# arm_shield_design_bottom_only.net
KiCad netlist of a schematic drawn in EAGLE
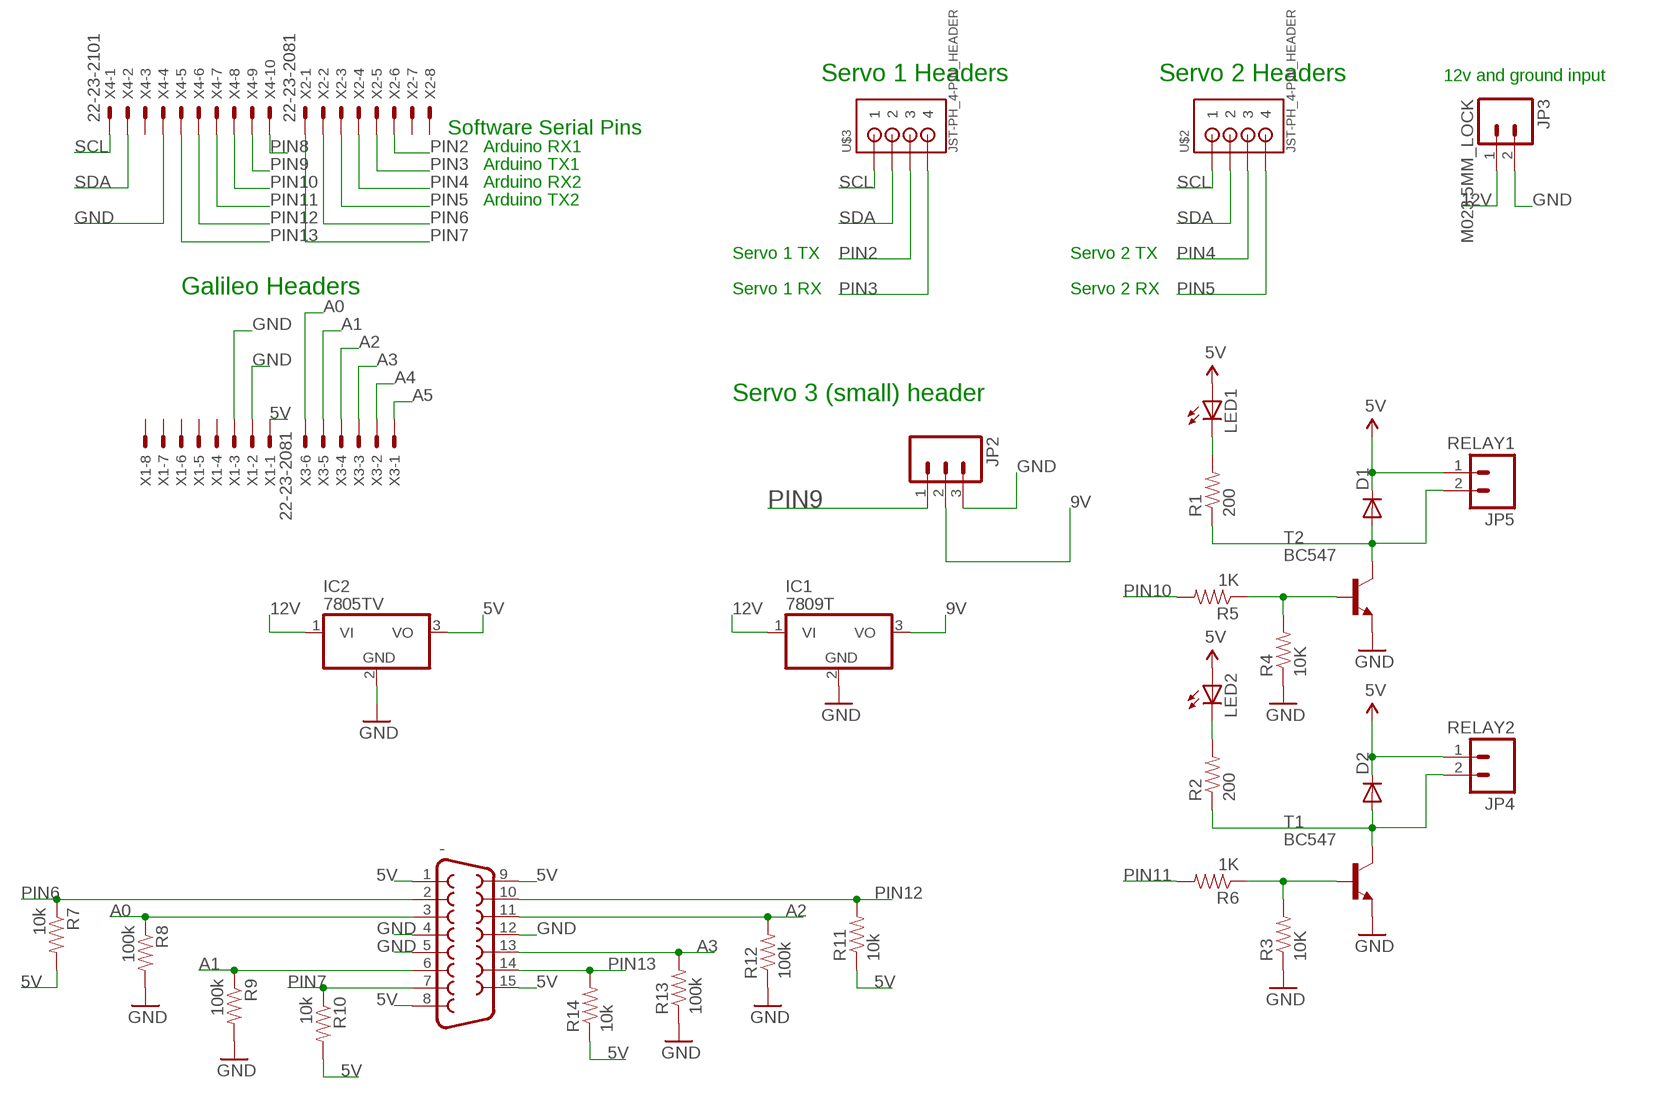
[diagram p0: schematic, sheet 1]

(export (version "E")
  (design (tool "Eeschema 10.0.6"))
  (components
    (comp (ref "-")
      (value "F15HP")
      (footprint "eagle-import:F15HP")
      (libsource (lib "eagle-import") (part "F15HP"))
    )
    (comp (ref "D1")
      (value "DIODE1N4148")
      (footprint "eagle-import:DIODE-1N4148")
      (libsource (lib "eagle-import") (part "DIODE1N4148"))
    )
    (comp (ref "D2")
      (value "DIODE1N4148")
      (footprint "eagle-import:DIODE-1N4148")
      (libsource (lib "eagle-import") (part "DIODE1N4148"))
    )
    (comp (ref "IC1")
      (value "7809T")
      (footprint "eagle-import:TO220V")
      (libsource (lib "eagle-import") (part "78TV05"))
    )
    (comp (ref "IC2")
      (value "7805TV")
      (footprint "eagle-import:TO220V")
      (libsource (lib "eagle-import") (part "78TV05"))
    )
    (comp (ref "JP2")
      (value "M03PTH")
      (footprint "eagle-import:1X03")
      (libsource (lib "eagle-import") (part "M03PTH"))
    )
    (comp (ref "JP3")
      (value "M023.5MM_LOCK")
      (footprint "eagle-import:SCREWTERMINAL-3.5MM-2_LOCK")
      (libsource (lib "eagle-import") (part "M023.5MM_LOCK"))
    )
    (comp (ref "JP4")
      (value "RELAY2")
      (footprint "eagle-import:SCREWTERMINAL-3.5MM-2_LOCK")
      (libsource (lib "eagle-import") (part "M023.5MM_LOCK"))
    )
    (comp (ref "JP5")
      (value "RELAY1")
      (footprint "eagle-import:SCREWTERMINAL-3.5MM-2_LOCK")
      (libsource (lib "eagle-import") (part "M023.5MM_LOCK"))
    )
    (comp (ref "LED1")
      (value "LED3MM")
      (footprint "eagle-import:LED3MM")
      (libsource (lib "eagle-import") (part "LED3MM"))
    )
    (comp (ref "LED2")
      (value "LED3MM")
      (footprint "eagle-import:LED3MM")
      (libsource (lib "eagle-import") (part "LED3MM"))
    )
    (comp (ref "R1")
      (value "200")
      (footprint "eagle-import:AXIAL-0.1")
      (libsource (lib "eagle-import") (part "RESISTORPTH-1/4W-VERT"))
    )
    (comp (ref "R2")
      (value "200")
      (footprint "eagle-import:AXIAL-0.1")
      (libsource (lib "eagle-import") (part "RESISTORPTH-1/4W-VERT"))
    )
    (comp (ref "R3")
      (value "10K")
      (footprint "eagle-import:AXIAL-0.1")
      (libsource (lib "eagle-import") (part "RESISTORPTH-1/4W-VERT"))
    )
    (comp (ref "R4")
      (value "10K")
      (footprint "eagle-import:AXIAL-0.1")
      (libsource (lib "eagle-import") (part "RESISTORPTH-1/4W-VERT"))
    )
    (comp (ref "R5")
      (value "1K")
      (footprint "eagle-import:AXIAL-0.1")
      (libsource (lib "eagle-import") (part "RESISTORPTH-1/4W-VERT"))
    )
    (comp (ref "R6")
      (value "1K")
      (footprint "eagle-import:AXIAL-0.1")
      (libsource (lib "eagle-import") (part "RESISTORPTH-1/4W-VERT"))
    )
    (comp (ref "R7")
      (value "10k")
      (footprint "eagle-import:AXIAL-0.1")
      (libsource (lib "eagle-import") (part "RESISTORPTH-1/4W-VERT"))
    )
    (comp (ref "R8")
      (value "100k")
      (footprint "eagle-import:AXIAL-0.1")
      (libsource (lib "eagle-import") (part "RESISTORPTH-1/4W-VERT"))
    )
    (comp (ref "R9")
      (value "100k")
      (footprint "eagle-import:AXIAL-0.1")
      (libsource (lib "eagle-import") (part "RESISTORPTH-1/4W-VERT"))
    )
    (comp (ref "R10")
      (value "10k")
      (footprint "eagle-import:AXIAL-0.1")
      (libsource (lib "eagle-import") (part "RESISTORPTH-1/4W-VERT"))
    )
    (comp (ref "R11")
      (value "10k")
      (footprint "eagle-import:AXIAL-0.1")
      (libsource (lib "eagle-import") (part "RESISTORPTH-1/4W-VERT"))
    )
    (comp (ref "R12")
      (value "100k")
      (footprint "eagle-import:AXIAL-0.1")
      (libsource (lib "eagle-import") (part "RESISTORPTH-1/4W-VERT"))
    )
    (comp (ref "R13")
      (value "100k")
      (footprint "eagle-import:AXIAL-0.1")
      (libsource (lib "eagle-import") (part "RESISTORPTH-1/4W-VERT"))
    )
    (comp (ref "R14")
      (value "10k")
      (footprint "eagle-import:AXIAL-0.1")
      (libsource (lib "eagle-import") (part "RESISTORPTH-1/4W-VERT"))
    )
    (comp (ref "T1")
      (value "BC547")
      (footprint "eagle-import:TO92")
      (libsource (lib "eagle-import") (part "BC547"))
    )
    (comp (ref "T2")
      (value "BC547")
      (footprint "eagle-import:TO92")
      (libsource (lib "eagle-import") (part "BC547"))
    )
    (comp (ref "U$2")
      (value "JST-PH_4-PIN_HEADER")
      (footprint "eagle-import:JST_B4B-PH_HEADER")
      (fields (field (name "MPN") "S4B-PH-K-S(LF)(SN)"))
      (libsource (lib "eagle-import") (part "JST-PH_4-PIN_HEADER"))
    )
    (comp (ref "U$3")
      (value "JST-PH_4-PIN_HEADER")
      (footprint "eagle-import:JST_B4B-PH_HEADER")
      (fields (field (name "MPN") "S4B-PH-K-S(LF)(SN)"))
      (libsource (lib "eagle-import") (part "JST-PH_4-PIN_HEADER"))
    )
    (comp (ref "X1")
      (value "22-23-2081")
      (footprint "eagle-import:22-23-2081")
      (fields (field (name "MF") "MOLEX"))
      (libsource (lib "eagle-import") (part "22-23-2081"))
    )
    (comp (ref "X2")
      (value "22-23-2081")
      (footprint "eagle-import:22-23-2081")
      (fields (field (name "MF") "MOLEX"))
      (libsource (lib "eagle-import") (part "22-23-2081"))
    )
    (comp (ref "X3")
      (value "22-23-2061")
      (footprint "eagle-import:22-23-2061")
      (fields (field (name "MF") "MOLEX"))
      (libsource (lib "eagle-import") (part "22-23-2061"))
    )
    (comp (ref "X4")
      (value "22-23-2101")
      (footprint "eagle-import:22-23-2101")
      (fields (field (name "MF") "MOLEX"))
      (libsource (lib "eagle-import") (part "22-23-2101"))
    )
  )
  (nets
    (net (code "1") (name "/9V") (class "Default")
      (node (ref "IC1") (pin "3") (pinfunction "VO_3") (pintype "passive"))
      (node (ref "JP2") (pin "2") (pinfunction "2_2") (pintype "passive"))
    )
    (net (code "2") (name "/12V") (class "Default")
      (node (ref "IC1") (pin "1") (pinfunction "VI_1") (pintype "input"))
      (node (ref "IC2") (pin "1") (pinfunction "VI_1") (pintype "input"))
      (node (ref "JP3") (pin "1") (pinfunction "1_1") (pintype "passive"))
    )
    (net (code "3") (name "/A0") (class "Default")
      (node (ref "-") (pin "3") (pinfunction "3_3") (pintype "passive"))
      (node (ref "R8") (pin "P$1") (pinfunction "1_P$1") (pintype "passive"))
      (node (ref "X3") (pin "6") (pinfunction "S_6") (pintype "passive"))
    )
    (net (code "4") (name "/A1") (class "Default")
      (node (ref "-") (pin "6") (pinfunction "6_6") (pintype "passive"))
      (node (ref "R9") (pin "P$1") (pinfunction "1_P$1") (pintype "passive"))
      (node (ref "X3") (pin "5") (pinfunction "S_5") (pintype "passive"))
    )
    (net (code "5") (name "/A2") (class "Default")
      (node (ref "-") (pin "11") (pinfunction "11_11") (pintype "passive"))
      (node (ref "R12") (pin "P$2") (pinfunction "2_P$2") (pintype "passive"))
      (node (ref "X3") (pin "4") (pinfunction "S_4") (pintype "passive"))
    )
    (net (code "6") (name "/A3") (class "Default")
      (node (ref "-") (pin "13") (pinfunction "13_13") (pintype "passive"))
      (node (ref "R13") (pin "P$2") (pinfunction "2_P$2") (pintype "passive"))
      (node (ref "X3") (pin "3") (pinfunction "S_3") (pintype "passive"))
    )
    (net (code "7") (name "/A4") (class "Default")
      (node (ref "X3") (pin "2") (pinfunction "S_2") (pintype "passive"))
    )
    (net (code "8") (name "/A5") (class "Default")
      (node (ref "X3") (pin "1") (pinfunction "S_1") (pintype "passive"))
    )
    (net (code "9") (name "/PIN2") (class "Default")
      (node (ref "U$3") (pin "P3") (pinfunction "3_P3") (pintype "bidirectional"))
      (node (ref "X2") (pin "6") (pinfunction "S_6") (pintype "passive"))
    )
    (net (code "10") (name "/PIN3") (class "Default")
      (node (ref "U$3") (pin "P4") (pinfunction "4_P4") (pintype "bidirectional"))
      (node (ref "X2") (pin "5") (pinfunction "S_5") (pintype "passive"))
    )
    (net (code "11") (name "/PIN4") (class "Default")
      (node (ref "U$2") (pin "P3") (pinfunction "3_P3") (pintype "bidirectional"))
      (node (ref "X2") (pin "4") (pinfunction "S_4") (pintype "passive"))
    )
    (net (code "12") (name "/PIN5") (class "Default")
      (node (ref "U$2") (pin "P4") (pinfunction "4_P4") (pintype "bidirectional"))
      (node (ref "X2") (pin "3") (pinfunction "S_3") (pintype "passive"))
    )
    (net (code "13") (name "/PIN6") (class "Default")
      (node (ref "-") (pin "2") (pinfunction "2_2") (pintype "passive"))
      (node (ref "R7") (pin "P$1") (pinfunction "1_P$1") (pintype "passive"))
      (node (ref "X2") (pin "2") (pinfunction "S_2") (pintype "passive"))
    )
    (net (code "14") (name "/PIN7") (class "Default")
      (node (ref "-") (pin "7") (pinfunction "7_7") (pintype "passive"))
      (node (ref "R10") (pin "P$1") (pinfunction "1_P$1") (pintype "passive"))
      (node (ref "X2") (pin "1") (pinfunction "S_1") (pintype "passive"))
    )
    (net (code "15") (name "/PIN8") (class "Default")
      (node (ref "X4") (pin "10") (pinfunction "S_10") (pintype "passive"))
    )
    (net (code "16") (name "/PIN9") (class "Default")
      (node (ref "JP2") (pin "1") (pinfunction "1_1") (pintype "passive"))
      (node (ref "X4") (pin "9") (pinfunction "S_9") (pintype "passive"))
    )
    (net (code "17") (name "/PIN10") (class "Default")
      (node (ref "R5") (pin "P$2") (pinfunction "2_P$2") (pintype "passive"))
      (node (ref "X4") (pin "8") (pinfunction "S_8") (pintype "passive"))
    )
    (net (code "18") (name "/PIN11") (class "Default")
      (node (ref "R6") (pin "P$2") (pinfunction "2_P$2") (pintype "passive"))
      (node (ref "X4") (pin "7") (pinfunction "S_7") (pintype "passive"))
    )
    (net (code "19") (name "/PIN12") (class "Default")
      (node (ref "-") (pin "10") (pinfunction "10_10") (pintype "passive"))
      (node (ref "R11") (pin "P$2") (pinfunction "2_P$2") (pintype "passive"))
      (node (ref "X4") (pin "6") (pinfunction "S_6") (pintype "passive"))
    )
    (net (code "20") (name "/PIN13") (class "Default")
      (node (ref "-") (pin "14") (pinfunction "14_14") (pintype "passive"))
      (node (ref "R14") (pin "P$2") (pinfunction "2_P$2") (pintype "passive"))
      (node (ref "X4") (pin "5") (pinfunction "S_5") (pintype "passive"))
    )
    (net (code "21") (name "/SCL") (class "Default")
      (node (ref "U$2") (pin "P1") (pinfunction "1_P1") (pintype "bidirectional"))
      (node (ref "U$3") (pin "P1") (pinfunction "1_P1") (pintype "bidirectional"))
      (node (ref "X4") (pin "1") (pinfunction "S_1") (pintype "passive"))
    )
    (net (code "22") (name "/SDA") (class "Default")
      (node (ref "U$2") (pin "P2") (pinfunction "2_P2") (pintype "bidirectional"))
      (node (ref "U$3") (pin "P2") (pinfunction "2_P2") (pintype "bidirectional"))
      (node (ref "X4") (pin "2") (pinfunction "S_2") (pintype "passive"))
    )
    (net (code "23") (name "5V") (class "Default")
      (node (ref "-") (pin "1") (pinfunction "1_1") (pintype "passive"))
      (node (ref "-") (pin "15") (pinfunction "15_15") (pintype "passive"))
      (node (ref "-") (pin "8") (pinfunction "8_8") (pintype "passive"))
      (node (ref "-") (pin "9") (pinfunction "9_9") (pintype "passive"))
      (node (ref "D1") (pin "C") (pinfunction "C_C") (pintype "passive"))
      (node (ref "D2") (pin "C") (pinfunction "C_C") (pintype "passive"))
      (node (ref "IC2") (pin "3") (pinfunction "VO_3") (pintype "passive"))
      (node (ref "JP4") (pin "1") (pinfunction "1_1") (pintype "passive"))
      (node (ref "JP5") (pin "1") (pinfunction "1_1") (pintype "passive"))
      (node (ref "LED1") (pin "A") (pinfunction "A_A") (pintype "passive"))
      (node (ref "LED2") (pin "A") (pinfunction "A_A") (pintype "passive"))
      (node (ref "R10") (pin "P$2") (pinfunction "2_P$2") (pintype "passive"))
      (node (ref "R11") (pin "P$1") (pinfunction "1_P$1") (pintype "passive"))
      (node (ref "R14") (pin "P$1") (pinfunction "1_P$1") (pintype "passive"))
      (node (ref "R7") (pin "P$2") (pinfunction "2_P$2") (pintype "passive"))
      (node (ref "X1") (pin "1") (pinfunction "S_1") (pintype "passive"))
    )
    (net (code "24") (name "GND") (class "Default")
      (node (ref "-") (pin "12") (pinfunction "12_12") (pintype "passive"))
      (node (ref "-") (pin "4") (pinfunction "4_4") (pintype "passive"))
      (node (ref "-") (pin "5") (pinfunction "5_5") (pintype "passive"))
      (node (ref "IC1") (pin "2") (pinfunction "GND_2") (pintype "passive"))
      (node (ref "IC2") (pin "2") (pinfunction "GND_2") (pintype "passive"))
      (node (ref "JP2") (pin "3") (pinfunction "3_3") (pintype "passive"))
      (node (ref "JP3") (pin "2") (pinfunction "2_2") (pintype "passive"))
      (node (ref "R12") (pin "P$1") (pinfunction "1_P$1") (pintype "passive"))
      (node (ref "R13") (pin "P$1") (pinfunction "1_P$1") (pintype "passive"))
      (node (ref "R3") (pin "P$1") (pinfunction "1_P$1") (pintype "passive"))
      (node (ref "R4") (pin "P$1") (pinfunction "1_P$1") (pintype "passive"))
      (node (ref "R8") (pin "P$2") (pinfunction "2_P$2") (pintype "passive"))
      (node (ref "R9") (pin "P$2") (pinfunction "2_P$2") (pintype "passive"))
      (node (ref "T1") (pin "1") (pinfunction "E_1") (pintype "passive"))
      (node (ref "T2") (pin "1") (pinfunction "E_1") (pintype "passive"))
      (node (ref "X1") (pin "2") (pinfunction "S_2") (pintype "passive"))
      (node (ref "X1") (pin "3") (pinfunction "S_3") (pintype "passive"))
      (node (ref "X4") (pin "4") (pinfunction "S_4") (pintype "passive"))
    )
    (net (code "25") (name "Net-(LED1-C)") (class "Default")
      (node (ref "LED1") (pin "K") (pinfunction "C_K") (pintype "passive"))
      (node (ref "R1") (pin "P$2") (pinfunction "2_P$2") (pintype "passive"))
    )
    (net (code "26") (name "Net-(LED2-C)") (class "Default")
      (node (ref "LED2") (pin "K") (pinfunction "C_K") (pintype "passive"))
      (node (ref "R2") (pin "P$2") (pinfunction "2_P$2") (pintype "passive"))
    )
    (net (code "27") (name "Net-(R1-1)") (class "Default")
      (node (ref "D1") (pin "A") (pinfunction "A_A") (pintype "passive"))
      (node (ref "JP5") (pin "2") (pinfunction "2_2") (pintype "passive"))
      (node (ref "R1") (pin "P$1") (pinfunction "1_P$1") (pintype "passive"))
      (node (ref "T2") (pin "3") (pinfunction "C_3") (pintype "passive"))
    )
    (net (code "28") (name "Net-(R2-1)") (class "Default")
      (node (ref "D2") (pin "A") (pinfunction "A_A") (pintype "passive"))
      (node (ref "JP4") (pin "2") (pinfunction "2_2") (pintype "passive"))
      (node (ref "R2") (pin "P$1") (pinfunction "1_P$1") (pintype "passive"))
      (node (ref "T1") (pin "3") (pinfunction "C_3") (pintype "passive"))
    )
    (net (code "29") (name "Net-(R3-2)") (class "Default")
      (node (ref "R3") (pin "P$2") (pinfunction "2_P$2") (pintype "passive"))
      (node (ref "R6") (pin "P$1") (pinfunction "1_P$1") (pintype "passive"))
      (node (ref "T1") (pin "2") (pinfunction "B_2") (pintype "passive"))
    )
    (net (code "30") (name "Net-(R4-2)") (class "Default")
      (node (ref "R4") (pin "P$2") (pinfunction "2_P$2") (pintype "passive"))
      (node (ref "R5") (pin "P$1") (pinfunction "1_P$1") (pintype "passive"))
      (node (ref "T2") (pin "2") (pinfunction "B_2") (pintype "passive"))
    )
    (net (code "31") (name "unconnected-(X1D-S-Pad4)") (class "Default")
      (node (ref "X1") (pin "4") (pinfunction "S_4") (pintype "passive"))
    )
    (net (code "32") (name "unconnected-(X1E-S-Pad5)") (class "Default")
      (node (ref "X1") (pin "5") (pinfunction "S_5") (pintype "passive"))
    )
    (net (code "33") (name "unconnected-(X1F-S-Pad6)") (class "Default")
      (node (ref "X1") (pin "6") (pinfunction "S_6") (pintype "passive"))
    )
    (net (code "34") (name "unconnected-(X1G-S-Pad7)") (class "Default")
      (node (ref "X1") (pin "7") (pinfunction "S_7") (pintype "passive"))
    )
    (net (code "35") (name "unconnected-(X1H-S-Pad8)") (class "Default")
      (node (ref "X1") (pin "8") (pinfunction "S_8") (pintype "passive"))
    )
    (net (code "36") (name "unconnected-(X2G-S-Pad7)") (class "Default")
      (node (ref "X2") (pin "7") (pinfunction "S_7") (pintype "passive"))
    )
    (net (code "37") (name "unconnected-(X2H-S-Pad8)") (class "Default")
      (node (ref "X2") (pin "8") (pinfunction "S_8") (pintype "passive"))
    )
    (net (code "38") (name "unconnected-(X4D-S-Pad3)") (class "Default")
      (node (ref "X4") (pin "3") (pinfunction "S_3") (pintype "passive"))
    )
  )
)
